# controler.net
KiCad netlist of a schematic drawn in EAGLE
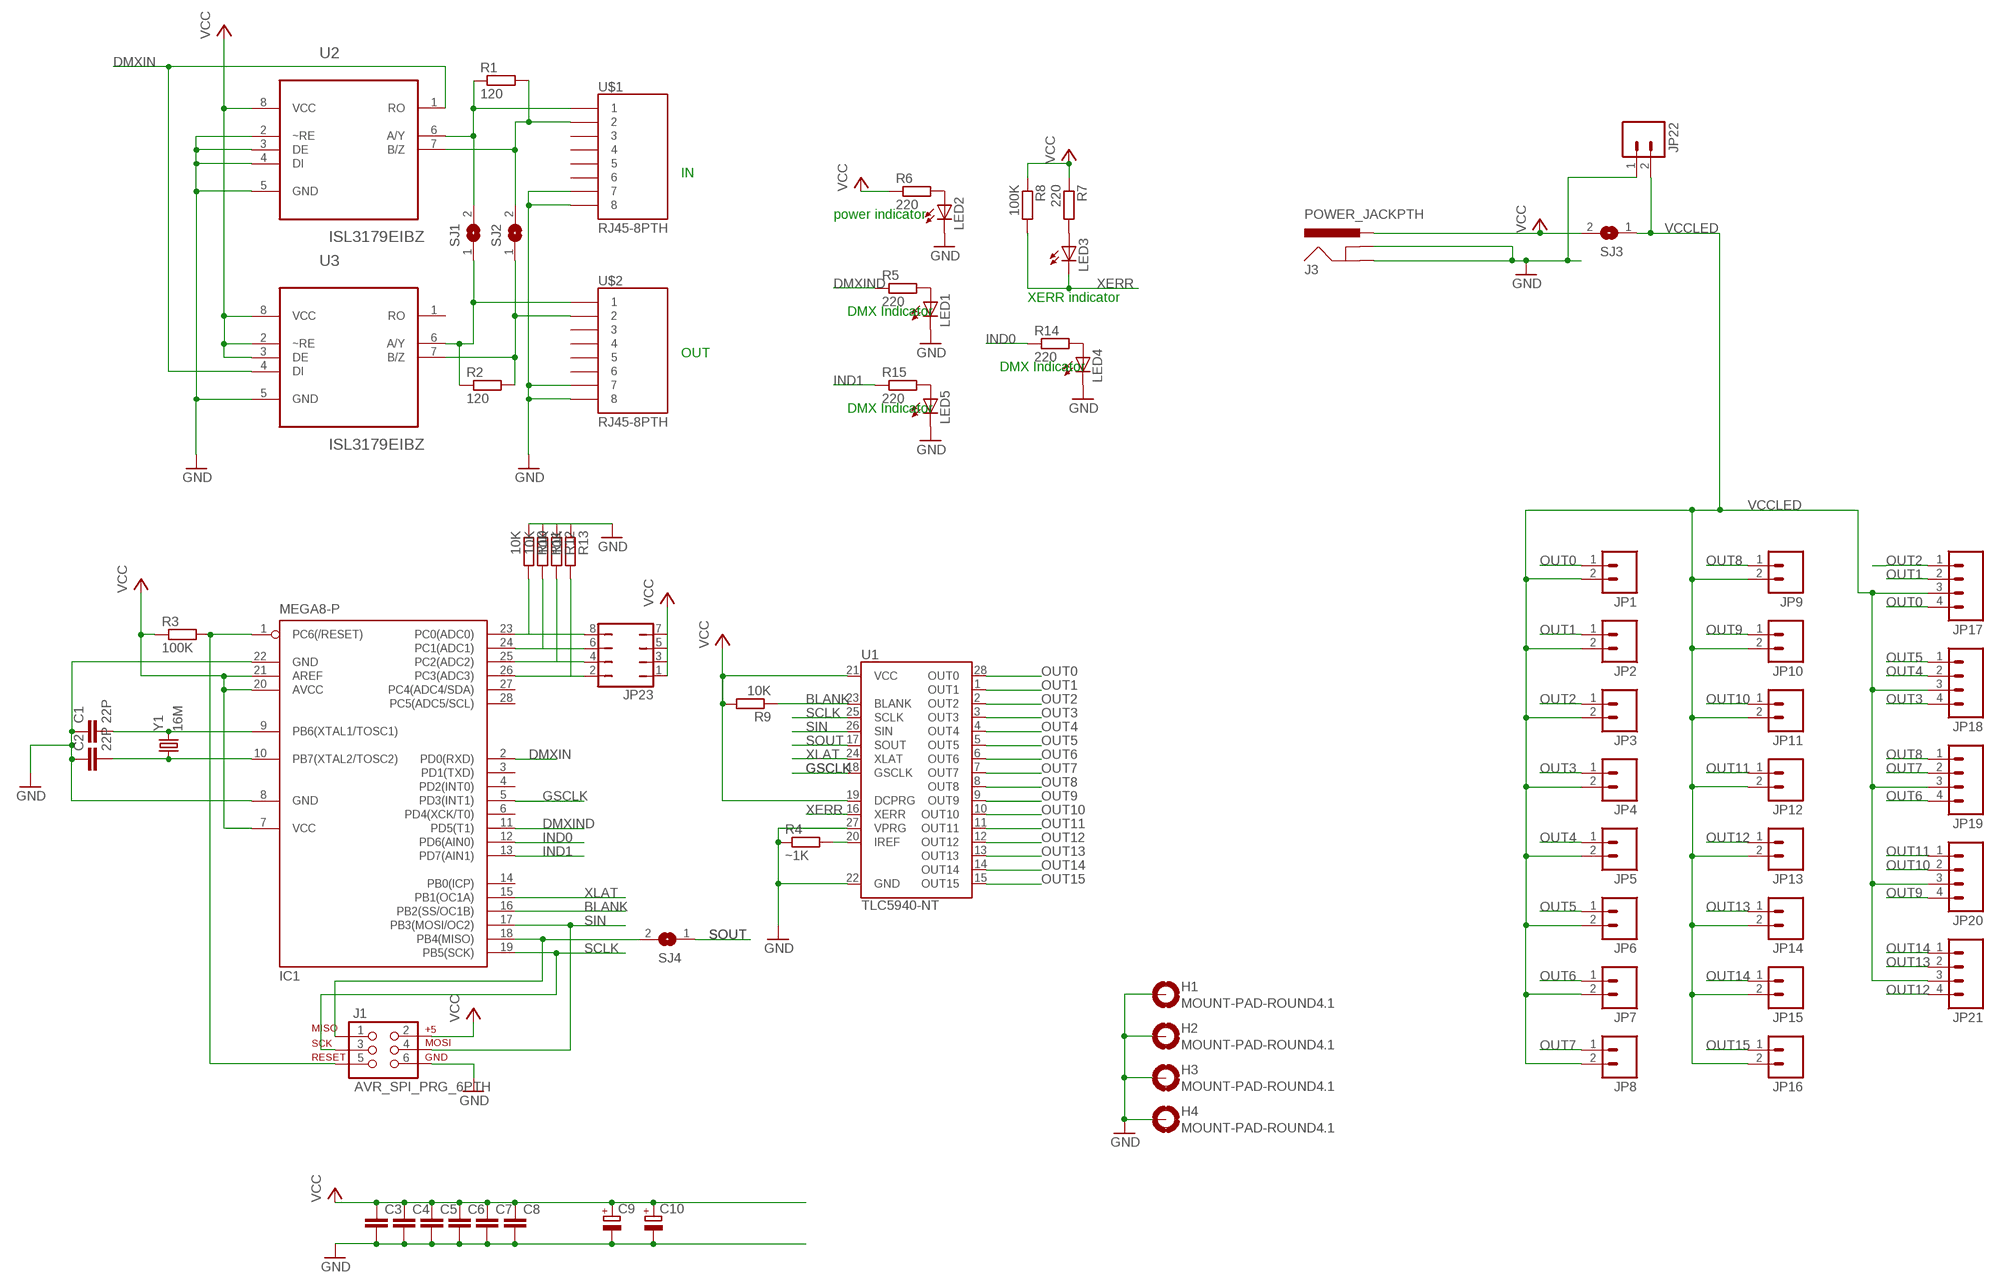
[diagram p0: schematic, sheet 1]

(export (version "E")
  (design (tool "Eeschema 10.0.6"))
  (components
    (comp (ref "C1")
      (value "22P")
      (footprint "eagle-import:C0603")
      (libsource (lib "eagle-import") (part "C-EUC0603"))
    )
    (comp (ref "C2")
      (value "22P")
      (footprint "eagle-import:C0603")
      (libsource (lib "eagle-import") (part "C-EUC0603"))
    )
    (comp (ref "C3")
      (value "C-EUC0603")
      (footprint "eagle-import:C0603")
      (libsource (lib "eagle-import") (part "resistor_C-EUC0603"))
    )
    (comp (ref "C4")
      (value "C-EUC0603")
      (footprint "eagle-import:C0603")
      (libsource (lib "eagle-import") (part "resistor_C-EUC0603"))
    )
    (comp (ref "C5")
      (value "C-EUC0603")
      (footprint "eagle-import:C0603")
      (libsource (lib "eagle-import") (part "resistor_C-EUC0603"))
    )
    (comp (ref "C6")
      (value "C-EUC0603")
      (footprint "eagle-import:C0603")
      (libsource (lib "eagle-import") (part "resistor_C-EUC0603"))
    )
    (comp (ref "C7")
      (value "C-EUC0603")
      (footprint "eagle-import:C0603")
      (libsource (lib "eagle-import") (part "resistor_C-EUC0603"))
    )
    (comp (ref "C8")
      (value "C-EUC0603")
      (footprint "eagle-import:C0603")
      (libsource (lib "eagle-import") (part "resistor_C-EUC0603"))
    )
    (comp (ref "C9")
      (value "CPOL-EUE2.5-6")
      (footprint "eagle-import:E2,5-6")
      (libsource (lib "eagle-import") (part "CPOL-EUE2.5-6"))
    )
    (comp (ref "C10")
      (value "CPOL-EUE3.5-10")
      (footprint "eagle-import:E3,5-10")
      (libsource (lib "eagle-import") (part "CPOL-EUE3.5-10"))
    )
    (comp (ref "H1")
      (value "MOUNT-PAD-ROUND4.1")
      (footprint "eagle-import:4,1-PAD")
      (libsource (lib "eagle-import") (part "MOUNT-PAD-ROUND4.1"))
    )
    (comp (ref "H2")
      (value "MOUNT-PAD-ROUND4.1")
      (footprint "eagle-import:4,1-PAD")
      (libsource (lib "eagle-import") (part "MOUNT-PAD-ROUND4.1"))
    )
    (comp (ref "H3")
      (value "MOUNT-PAD-ROUND4.1")
      (footprint "eagle-import:4,1-PAD")
      (libsource (lib "eagle-import") (part "MOUNT-PAD-ROUND4.1"))
    )
    (comp (ref "H4")
      (value "MOUNT-PAD-ROUND4.1")
      (footprint "eagle-import:4,1-PAD")
      (libsource (lib "eagle-import") (part "MOUNT-PAD-ROUND4.1"))
    )
    (comp (ref "IC1")
      (value "MEGA8-P")
      (footprint "eagle-import:DIL28-3")
      (libsource (lib "eagle-import") (part "MEGA8-P"))
    )
    (comp (ref "J1")
      (value "AVR_SPI_PRG_6PTH")
      (footprint "eagle-import:2X3")
      (libsource (lib "eagle-import") (part "AVR_SPI_PRG_6PTH"))
    )
    (comp (ref "J3")
      (value "POWER_JACKPTH")
      (footprint "eagle-import:POWER_JACK_PTH")
      (libsource (lib "eagle-import") (part "POWER_JACKPTH"))
    )
    (comp (ref "JP1")
      (value "M02POLAR")
      (footprint "eagle-import:MOLEX-1X2")
      (libsource (lib "eagle-import") (part "M02POLAR"))
    )
    (comp (ref "JP2")
      (value "M02POLAR")
      (footprint "eagle-import:MOLEX-1X2")
      (libsource (lib "eagle-import") (part "M02POLAR"))
    )
    (comp (ref "JP3")
      (value "M02POLAR")
      (footprint "eagle-import:MOLEX-1X2")
      (libsource (lib "eagle-import") (part "M02POLAR"))
    )
    (comp (ref "JP4")
      (value "M02POLAR")
      (footprint "eagle-import:MOLEX-1X2")
      (libsource (lib "eagle-import") (part "M02POLAR"))
    )
    (comp (ref "JP5")
      (value "M02POLAR")
      (footprint "eagle-import:MOLEX-1X2")
      (libsource (lib "eagle-import") (part "M02POLAR"))
    )
    (comp (ref "JP6")
      (value "M02POLAR")
      (footprint "eagle-import:MOLEX-1X2")
      (libsource (lib "eagle-import") (part "M02POLAR"))
    )
    (comp (ref "JP7")
      (value "M02POLAR")
      (footprint "eagle-import:MOLEX-1X2")
      (libsource (lib "eagle-import") (part "M02POLAR"))
    )
    (comp (ref "JP8")
      (value "M02POLAR")
      (footprint "eagle-import:MOLEX-1X2")
      (libsource (lib "eagle-import") (part "M02POLAR"))
    )
    (comp (ref "JP9")
      (value "M02POLAR")
      (footprint "eagle-import:MOLEX-1X2")
      (libsource (lib "eagle-import") (part "M02POLAR"))
    )
    (comp (ref "JP10")
      (value "M02POLAR")
      (footprint "eagle-import:MOLEX-1X2")
      (libsource (lib "eagle-import") (part "M02POLAR"))
    )
    (comp (ref "JP11")
      (value "M02POLAR")
      (footprint "eagle-import:MOLEX-1X2")
      (libsource (lib "eagle-import") (part "M02POLAR"))
    )
    (comp (ref "JP12")
      (value "M02POLAR")
      (footprint "eagle-import:MOLEX-1X2")
      (libsource (lib "eagle-import") (part "M02POLAR"))
    )
    (comp (ref "JP13")
      (value "M02POLAR")
      (footprint "eagle-import:MOLEX-1X2")
      (libsource (lib "eagle-import") (part "M02POLAR"))
    )
    (comp (ref "JP14")
      (value "M02POLAR")
      (footprint "eagle-import:MOLEX-1X2")
      (libsource (lib "eagle-import") (part "M02POLAR"))
    )
    (comp (ref "JP15")
      (value "M02POLAR")
      (footprint "eagle-import:MOLEX-1X2")
      (libsource (lib "eagle-import") (part "M02POLAR"))
    )
    (comp (ref "JP16")
      (value "M02POLAR")
      (footprint "eagle-import:MOLEX-1X2")
      (libsource (lib "eagle-import") (part "M02POLAR"))
    )
    (comp (ref "JP17")
      (value "M04POLAR")
      (footprint "eagle-import:MOLEX-1X4")
      (libsource (lib "eagle-import") (part "M04POLAR"))
    )
    (comp (ref "JP18")
      (value "M04POLAR")
      (footprint "eagle-import:MOLEX-1X4")
      (libsource (lib "eagle-import") (part "M04POLAR"))
    )
    (comp (ref "JP19")
      (value "M04POLAR")
      (footprint "eagle-import:MOLEX-1X4")
      (libsource (lib "eagle-import") (part "M04POLAR"))
    )
    (comp (ref "JP20")
      (value "M04POLAR")
      (footprint "eagle-import:MOLEX-1X4")
      (libsource (lib "eagle-import") (part "M04POLAR"))
    )
    (comp (ref "JP21")
      (value "M04POLAR")
      (footprint "eagle-import:MOLEX-1X4")
      (libsource (lib "eagle-import") (part "M04POLAR"))
    )
    (comp (ref "JP22")
      (value "M023.5MM")
      (footprint "eagle-import:SCREWTERMINAL-3.5MM-2")
      (libsource (lib "eagle-import") (part "M023.5MM"))
    )
    (comp (ref "JP23")
      (value "JP4Q")
      (footprint "eagle-import:JP4Q")
      (libsource (lib "eagle-import") (part "JP4Q"))
    )
    (comp (ref "LED1")
      (value "LEDCHIPLED_0603")
      (footprint "eagle-import:CHIPLED_0603")
      (libsource (lib "eagle-import") (part "LEDCHIPLED_0603"))
    )
    (comp (ref "LED2")
      (value "LEDCHIPLED_0603")
      (footprint "eagle-import:CHIPLED_0603")
      (libsource (lib "eagle-import") (part "LEDCHIPLED_0603"))
    )
    (comp (ref "LED3")
      (value "LEDCHIPLED_0603")
      (footprint "eagle-import:CHIPLED_0603")
      (libsource (lib "eagle-import") (part "LEDCHIPLED_0603"))
    )
    (comp (ref "LED4")
      (value "LEDCHIPLED_0603")
      (footprint "eagle-import:CHIPLED_0603")
      (libsource (lib "eagle-import") (part "LEDCHIPLED_0603"))
    )
    (comp (ref "LED5")
      (value "LEDCHIPLED_0603")
      (footprint "eagle-import:CHIPLED_0603")
      (libsource (lib "eagle-import") (part "LEDCHIPLED_0603"))
    )
    (comp (ref "R1")
      (value "120")
      (footprint "eagle-import:R0603")
      (libsource (lib "eagle-import") (part "R-EU_R0603"))
    )
    (comp (ref "R2")
      (value "120")
      (footprint "eagle-import:R0603")
      (libsource (lib "eagle-import") (part "R-EU_R0603"))
    )
    (comp (ref "R3")
      (value "100K")
      (footprint "eagle-import:R0603")
      (libsource (lib "eagle-import") (part "resistor_R-EU_R0603"))
    )
    (comp (ref "R4")
      (value "~1K")
      (footprint "eagle-import:R0603")
      (libsource (lib "eagle-import") (part "resistor_R-EU_R0603"))
    )
    (comp (ref "R5")
      (value "220")
      (footprint "eagle-import:R0603")
      (libsource (lib "eagle-import") (part "resistor_R-EU_R0603"))
    )
    (comp (ref "R6")
      (value "220")
      (footprint "eagle-import:R0603")
      (libsource (lib "eagle-import") (part "resistor_R-EU_R0603"))
    )
    (comp (ref "R7")
      (value "220")
      (footprint "eagle-import:R0603")
      (libsource (lib "eagle-import") (part "resistor_R-EU_R0603"))
    )
    (comp (ref "R8")
      (value "100K")
      (footprint "eagle-import:R0603")
      (libsource (lib "eagle-import") (part "resistor_R-EU_R0603"))
    )
    (comp (ref "R9")
      (value "10K")
      (footprint "eagle-import:R0603")
      (libsource (lib "eagle-import") (part "resistor_R-EU_R0603"))
    )
    (comp (ref "R10")
      (value "10K")
      (footprint "eagle-import:R0603")
      (libsource (lib "eagle-import") (part "resistor_R-EU_R0603"))
    )
    (comp (ref "R11")
      (value "10K")
      (footprint "eagle-import:R0603")
      (libsource (lib "eagle-import") (part "resistor_R-EU_R0603"))
    )
    (comp (ref "R12")
      (value "10K")
      (footprint "eagle-import:R0603")
      (libsource (lib "eagle-import") (part "resistor_R-EU_R0603"))
    )
    (comp (ref "R13")
      (value "10K")
      (footprint "eagle-import:R0603")
      (libsource (lib "eagle-import") (part "resistor_R-EU_R0603"))
    )
    (comp (ref "R14")
      (value "220")
      (footprint "eagle-import:R0603")
      (libsource (lib "eagle-import") (part "resistor_R-EU_R0603"))
    )
    (comp (ref "R15")
      (value "220")
      (footprint "eagle-import:R0603")
      (libsource (lib "eagle-import") (part "resistor_R-EU_R0603"))
    )
    (comp (ref "SJ1") (value "SJ") (footprint "eagle-import:SJ") (libsource (lib "eagle-import") (part "SJ")))
    (comp (ref "SJ2") (value "SJ") (footprint "eagle-import:SJ") (libsource (lib "eagle-import") (part "SJ")))
    (comp (ref "SJ3")
      (value "SJW")
      (footprint "eagle-import:SJW")
      (libsource (lib "eagle-import") (part "SJW"))
    )
    (comp (ref "SJ4") (value "SJ") (footprint "eagle-import:SJ") (libsource (lib "eagle-import") (part "SJ")))
    (comp (ref "U$1")
      (value "RJ45-8PTH")
      (footprint "eagle-import:RJ45-8")
      (libsource (lib "eagle-import") (part "RJ45-8PTH"))
    )
    (comp (ref "U$2")
      (value "RJ45-8PTH")
      (footprint "eagle-import:RJ45-8")
      (libsource (lib "eagle-import") (part "RJ45-8PTH"))
    )
    (comp (ref "U1")
      (value "TLC5940-NT")
      (footprint "eagle-import:DIL28-3")
      (libsource (lib "eagle-import") (part "TLC5940-NT"))
    )
    (comp (ref "U2")
      (value "ISL3179EIBZ")
      (footprint "eagle-import:SOIC127P600X175-8N")
      (libsource (lib "eagle-import") (part "ISL3179EIBZ"))
    )
    (comp (ref "U3")
      (value "ISL3179EIBZ")
      (footprint "eagle-import:SOIC127P600X175-8N")
      (libsource (lib "eagle-import") (part "ISL3179EIBZ"))
    )
    (comp (ref "Y1")
      (value "16M")
      (footprint "eagle-import:HC49US")
      (libsource (lib "eagle-import") (part "CRYSTALHC49US"))
    )
  )
  (nets
    (net (code "1") (name "/BLANK") (class "Default")
      (node (ref "IC1") (pin "16") (pinfunction "PB2(SS/OC1B)_16") (pintype "bidirectional"))
      (node (ref "R9") (pin "1") (pinfunction "1_1") (pintype "passive"))
      (node (ref "U1") (pin "23") (pinfunction "BLANK_23") (pintype "bidirectional"))
    )
    (net (code "2") (name "/DMXIN") (class "Default")
      (node (ref "IC1") (pin "2") (pinfunction "PD0(RXD)_2") (pintype "bidirectional"))
      (node (ref "U2") (pin "1") (pinfunction "RO_1") (pintype "output"))
      (node (ref "U3") (pin "4") (pinfunction "DI_4") (pintype "input"))
    )
    (net (code "3") (name "/DMXIND") (class "Default")
      (node (ref "IC1") (pin "11") (pinfunction "PD5(T1)_11") (pintype "bidirectional"))
      (node (ref "R5") (pin "1") (pinfunction "1_1") (pintype "passive"))
    )
    (net (code "4") (name "/GSCLK") (class "Default")
      (node (ref "IC1") (pin "5") (pinfunction "PD3(INT1)_5") (pintype "bidirectional"))
      (node (ref "U1") (pin "18") (pinfunction "GSCLK_18") (pintype "bidirectional"))
    )
    (net (code "5") (name "/IND0") (class "Default")
      (node (ref "IC1") (pin "12") (pinfunction "PD6(AIN0)_12") (pintype "bidirectional"))
      (node (ref "R14") (pin "1") (pinfunction "1_1") (pintype "passive"))
    )
    (net (code "6") (name "/IND1") (class "Default")
      (node (ref "IC1") (pin "13") (pinfunction "PD7(AIN1)_13") (pintype "bidirectional"))
      (node (ref "R15") (pin "1") (pinfunction "1_1") (pintype "passive"))
    )
    (net (code "7") (name "/OUT0") (class "Default")
      (node (ref "JP1") (pin "1") (pinfunction "1_1") (pintype "passive"))
      (node (ref "JP17") (pin "4") (pinfunction "4_4") (pintype "passive"))
      (node (ref "U1") (pin "28") (pinfunction "OUT0_28") (pintype "bidirectional"))
    )
    (net (code "8") (name "/OUT1") (class "Default")
      (node (ref "JP17") (pin "2") (pinfunction "2_2") (pintype "passive"))
      (node (ref "JP2") (pin "1") (pinfunction "1_1") (pintype "passive"))
      (node (ref "U1") (pin "1") (pinfunction "OUT1_1") (pintype "bidirectional"))
    )
    (net (code "9") (name "/OUT2") (class "Default")
      (node (ref "JP17") (pin "1") (pinfunction "1_1") (pintype "passive"))
      (node (ref "JP3") (pin "1") (pinfunction "1_1") (pintype "passive"))
      (node (ref "U1") (pin "2") (pinfunction "OUT2_2") (pintype "bidirectional"))
    )
    (net (code "10") (name "/OUT3") (class "Default")
      (node (ref "JP18") (pin "4") (pinfunction "4_4") (pintype "passive"))
      (node (ref "JP4") (pin "1") (pinfunction "1_1") (pintype "passive"))
      (node (ref "U1") (pin "3") (pinfunction "OUT3_3") (pintype "bidirectional"))
    )
    (net (code "11") (name "/OUT4") (class "Default")
      (node (ref "JP18") (pin "2") (pinfunction "2_2") (pintype "passive"))
      (node (ref "JP5") (pin "1") (pinfunction "1_1") (pintype "passive"))
      (node (ref "U1") (pin "4") (pinfunction "OUT4_4") (pintype "bidirectional"))
    )
    (net (code "12") (name "/OUT5") (class "Default")
      (node (ref "JP18") (pin "1") (pinfunction "1_1") (pintype "passive"))
      (node (ref "JP6") (pin "1") (pinfunction "1_1") (pintype "passive"))
      (node (ref "U1") (pin "5") (pinfunction "OUT5_5") (pintype "bidirectional"))
    )
    (net (code "13") (name "/OUT6") (class "Default")
      (node (ref "JP19") (pin "4") (pinfunction "4_4") (pintype "passive"))
      (node (ref "JP7") (pin "1") (pinfunction "1_1") (pintype "passive"))
      (node (ref "U1") (pin "6") (pinfunction "OUT6_6") (pintype "bidirectional"))
    )
    (net (code "14") (name "/OUT7") (class "Default")
      (node (ref "JP19") (pin "2") (pinfunction "2_2") (pintype "passive"))
      (node (ref "JP8") (pin "1") (pinfunction "1_1") (pintype "passive"))
      (node (ref "U1") (pin "7") (pinfunction "OUT7_7") (pintype "bidirectional"))
    )
    (net (code "15") (name "/OUT8") (class "Default")
      (node (ref "JP19") (pin "1") (pinfunction "1_1") (pintype "passive"))
      (node (ref "JP9") (pin "1") (pinfunction "1_1") (pintype "passive"))
      (node (ref "U1") (pin "8") (pinfunction "OUT8_8") (pintype "bidirectional"))
    )
    (net (code "16") (name "/OUT9") (class "Default")
      (node (ref "JP10") (pin "1") (pinfunction "1_1") (pintype "passive"))
      (node (ref "JP20") (pin "4") (pinfunction "4_4") (pintype "passive"))
      (node (ref "U1") (pin "9") (pinfunction "OUT9_9") (pintype "bidirectional"))
    )
    (net (code "17") (name "/OUT10") (class "Default")
      (node (ref "JP11") (pin "1") (pinfunction "1_1") (pintype "passive"))
      (node (ref "JP20") (pin "2") (pinfunction "2_2") (pintype "passive"))
      (node (ref "U1") (pin "10") (pinfunction "OUT10_10") (pintype "bidirectional"))
    )
    (net (code "18") (name "/OUT11") (class "Default")
      (node (ref "JP12") (pin "1") (pinfunction "1_1") (pintype "passive"))
      (node (ref "JP20") (pin "1") (pinfunction "1_1") (pintype "passive"))
      (node (ref "U1") (pin "11") (pinfunction "OUT11_11") (pintype "bidirectional"))
    )
    (net (code "19") (name "/OUT12") (class "Default")
      (node (ref "JP13") (pin "1") (pinfunction "1_1") (pintype "passive"))
      (node (ref "JP21") (pin "4") (pinfunction "4_4") (pintype "passive"))
      (node (ref "U1") (pin "12") (pinfunction "OUT12_12") (pintype "bidirectional"))
    )
    (net (code "20") (name "/OUT13") (class "Default")
      (node (ref "JP14") (pin "1") (pinfunction "1_1") (pintype "passive"))
      (node (ref "JP21") (pin "2") (pinfunction "2_2") (pintype "passive"))
      (node (ref "U1") (pin "13") (pinfunction "OUT13_13") (pintype "bidirectional"))
    )
    (net (code "21") (name "/OUT14") (class "Default")
      (node (ref "JP15") (pin "1") (pinfunction "1_1") (pintype "passive"))
      (node (ref "JP21") (pin "1") (pinfunction "1_1") (pintype "passive"))
      (node (ref "U1") (pin "14") (pinfunction "OUT14_14") (pintype "bidirectional"))
    )
    (net (code "22") (name "/OUT15") (class "Default")
      (node (ref "JP16") (pin "1") (pinfunction "1_1") (pintype "passive"))
      (node (ref "U1") (pin "15") (pinfunction "OUT15_15") (pintype "bidirectional"))
    )
    (net (code "23") (name "/SCLK") (class "Default")
      (node (ref "IC1") (pin "19") (pinfunction "PB5(SCK)_19") (pintype "bidirectional"))
      (node (ref "J1") (pin "3") (pinfunction "3_3") (pintype "passive"))
      (node (ref "U1") (pin "25") (pinfunction "SCLK_25") (pintype "bidirectional"))
    )
    (net (code "24") (name "/SIN") (class "Default")
      (node (ref "IC1") (pin "17") (pinfunction "PB3(MOSI/OC2)_17") (pintype "bidirectional"))
      (node (ref "J1") (pin "4") (pinfunction "4_4") (pintype "passive"))
      (node (ref "U1") (pin "26") (pinfunction "SIN_26") (pintype "bidirectional"))
    )
    (net (code "25") (name "/SOUT") (class "Default")
      (node (ref "SJ4") (pin "1") (pinfunction "1_1") (pintype "passive"))
      (node (ref "U1") (pin "17") (pinfunction "SOUT_17") (pintype "bidirectional"))
    )
    (net (code "26") (name "/VCCLED") (class "Default")
      (node (ref "JP1") (pin "2") (pinfunction "2_2") (pintype "passive"))
      (node (ref "JP10") (pin "2") (pinfunction "2_2") (pintype "passive"))
      (node (ref "JP11") (pin "2") (pinfunction "2_2") (pintype "passive"))
      (node (ref "JP12") (pin "2") (pinfunction "2_2") (pintype "passive"))
      (node (ref "JP13") (pin "2") (pinfunction "2_2") (pintype "passive"))
      (node (ref "JP14") (pin "2") (pinfunction "2_2") (pintype "passive"))
      (node (ref "JP15") (pin "2") (pinfunction "2_2") (pintype "passive"))
      (node (ref "JP16") (pin "2") (pinfunction "2_2") (pintype "passive"))
      (node (ref "JP17") (pin "3") (pinfunction "3_3") (pintype "passive"))
      (node (ref "JP18") (pin "3") (pinfunction "3_3") (pintype "passive"))
      (node (ref "JP19") (pin "3") (pinfunction "3_3") (pintype "passive"))
      (node (ref "JP2") (pin "2") (pinfunction "2_2") (pintype "passive"))
      (node (ref "JP20") (pin "3") (pinfunction "3_3") (pintype "passive"))
      (node (ref "JP21") (pin "3") (pinfunction "3_3") (pintype "passive"))
      (node (ref "JP22") (pin "2") (pinfunction "2_2") (pintype "passive"))
      (node (ref "JP3") (pin "2") (pinfunction "2_2") (pintype "passive"))
      (node (ref "JP4") (pin "2") (pinfunction "2_2") (pintype "passive"))
      (node (ref "JP5") (pin "2") (pinfunction "2_2") (pintype "passive"))
      (node (ref "JP6") (pin "2") (pinfunction "2_2") (pintype "passive"))
      (node (ref "JP7") (pin "2") (pinfunction "2_2") (pintype "passive"))
      (node (ref "JP8") (pin "2") (pinfunction "2_2") (pintype "passive"))
      (node (ref "JP9") (pin "2") (pinfunction "2_2") (pintype "passive"))
      (node (ref "SJ3") (pin "1") (pinfunction "1_1") (pintype "passive"))
    )
    (net (code "27") (name "/XERR") (class "Default")
      (node (ref "LED3") (pin "C") (pinfunction "C_C") (pintype "passive"))
      (node (ref "R8") (pin "2") (pinfunction "2_2") (pintype "passive"))
      (node (ref "U1") (pin "16") (pinfunction "XERR_16") (pintype "bidirectional"))
    )
    (net (code "28") (name "/XLAT") (class "Default")
      (node (ref "IC1") (pin "15") (pinfunction "PB1(OC1A)_15") (pintype "bidirectional"))
      (node (ref "U1") (pin "24") (pinfunction "XLAT_24") (pintype "bidirectional"))
    )
    (net (code "29") (name "GND") (class "Default")
      (node (ref "C1") (pin "1") (pinfunction "1_1") (pintype "passive"))
      (node (ref "C10") (pin "-") (pinfunction "-_-") (pintype "passive"))
      (node (ref "C2") (pin "1") (pinfunction "1_1") (pintype "passive"))
      (node (ref "C3") (pin "2") (pinfunction "2_2") (pintype "passive"))
      (node (ref "C4") (pin "2") (pinfunction "2_2") (pintype "passive"))
      (node (ref "C5") (pin "2") (pinfunction "2_2") (pintype "passive"))
      (node (ref "C6") (pin "2") (pinfunction "2_2") (pintype "passive"))
      (node (ref "C7") (pin "2") (pinfunction "2_2") (pintype "passive"))
      (node (ref "C8") (pin "2") (pinfunction "2_2") (pintype "passive"))
      (node (ref "C9") (pin "-") (pinfunction "-_-") (pintype "passive"))
      (node (ref "H1") (pin "B4,1") (pinfunction "MOUNT_B4,1") (pintype "passive"))
      (node (ref "H2") (pin "B4,1") (pinfunction "MOUNT_B4,1") (pintype "passive"))
      (node (ref "H3") (pin "B4,1") (pinfunction "MOUNT_B4,1") (pintype "passive"))
      (node (ref "H4") (pin "B4,1") (pinfunction "MOUNT_B4,1") (pintype "passive"))
      (node (ref "IC1") (pin "22") (pinfunction "GND_22") (pintype "power_in"))
      (node (ref "IC1") (pin "8") (pinfunction "GND_8") (pintype "power_in"))
      (node (ref "J1") (pin "6") (pinfunction "6_6") (pintype "passive"))
      (node (ref "J3") (pin "GND") (pinfunction "GND_GND") (pintype "bidirectional"))
      (node (ref "J3") (pin "GNDBREAK") (pinfunction "GNDBREAK_GNDBREAK") (pintype "bidirectional"))
      (node (ref "JP22") (pin "1") (pinfunction "1_1") (pintype "passive"))
      (node (ref "LED1") (pin "C") (pinfunction "C_C") (pintype "passive"))
      (node (ref "LED2") (pin "C") (pinfunction "C_C") (pintype "passive"))
      (node (ref "LED4") (pin "C") (pinfunction "C_C") (pintype "passive"))
      (node (ref "LED5") (pin "C") (pinfunction "C_C") (pintype "passive"))
      (node (ref "R10") (pin "1") (pinfunction "1_1") (pintype "passive"))
      (node (ref "R11") (pin "1") (pinfunction "1_1") (pintype "passive"))
      (node (ref "R12") (pin "1") (pinfunction "1_1") (pintype "passive"))
      (node (ref "R13") (pin "1") (pinfunction "1_1") (pintype "passive"))
      (node (ref "R4") (pin "1") (pinfunction "1_1") (pintype "passive"))
      (node (ref "U$1") (pin "7") (pinfunction "7_7") (pintype "bidirectional"))
      (node (ref "U$1") (pin "8") (pinfunction "8_8") (pintype "bidirectional"))
      (node (ref "U$2") (pin "7") (pinfunction "7_7") (pintype "bidirectional"))
      (node (ref "U$2") (pin "8") (pinfunction "8_8") (pintype "bidirectional"))
      (node (ref "U1") (pin "22") (pinfunction "GND_22") (pintype "bidirectional"))
      (node (ref "U1") (pin "27") (pinfunction "VPRG_27") (pintype "bidirectional"))
      (node (ref "U2") (pin "2") (pinfunction "~{RE}_2") (pintype "input"))
      (node (ref "U2") (pin "3") (pinfunction "DE_3") (pintype "input"))
      (node (ref "U2") (pin "4") (pinfunction "DI_4") (pintype "input"))
      (node (ref "U2") (pin "5") (pinfunction "GND_5") (pintype "passive"))
      (node (ref "U3") (pin "5") (pinfunction "GND_5") (pintype "passive"))
    )
    (net (code "30") (name "Net-(IC1-PB4(MISO))") (class "Default")
      (node (ref "IC1") (pin "18") (pinfunction "PB4(MISO)_18") (pintype "bidirectional"))
      (node (ref "J1") (pin "1") (pinfunction "1_1") (pintype "passive"))
      (node (ref "SJ4") (pin "2") (pinfunction "2_2") (pintype "passive"))
    )
    (net (code "31") (name "Net-(IC1-PB6(XTAL1{slash}TOSC1))") (class "Default")
      (node (ref "C1") (pin "2") (pinfunction "2_2") (pintype "passive"))
      (node (ref "IC1") (pin "9") (pinfunction "PB6(XTAL1/TOSC1)_9") (pintype "bidirectional"))
      (node (ref "Y1") (pin "2") (pinfunction "2_2") (pintype "passive"))
    )
    (net (code "32") (name "Net-(IC1-PB7(XTAL2{slash}TOSC2))") (class "Default")
      (node (ref "C2") (pin "2") (pinfunction "2_2") (pintype "passive"))
      (node (ref "IC1") (pin "10") (pinfunction "PB7(XTAL2/TOSC2)_10") (pintype "bidirectional"))
      (node (ref "Y1") (pin "1") (pinfunction "1_1") (pintype "passive"))
    )
    (net (code "33") (name "Net-(IC1-PC0(ADC0))") (class "Default")
      (node (ref "IC1") (pin "23") (pinfunction "PC0(ADC0)_23") (pintype "bidirectional"))
      (node (ref "JP23") (pin "8") (pinfunction "8_8") (pintype "passive"))
      (node (ref "R10") (pin "2") (pinfunction "2_2") (pintype "passive"))
    )
    (net (code "34") (name "Net-(IC1-PC1(ADC1))") (class "Default")
      (node (ref "IC1") (pin "24") (pinfunction "PC1(ADC1)_24") (pintype "bidirectional"))
      (node (ref "JP23") (pin "6") (pinfunction "6_6") (pintype "passive"))
      (node (ref "R11") (pin "2") (pinfunction "2_2") (pintype "passive"))
    )
    (net (code "35") (name "Net-(IC1-PC2(ADC2))") (class "Default")
      (node (ref "IC1") (pin "25") (pinfunction "PC2(ADC2)_25") (pintype "bidirectional"))
      (node (ref "JP23") (pin "4") (pinfunction "4_4") (pintype "passive"))
      (node (ref "R12") (pin "2") (pinfunction "2_2") (pintype "passive"))
    )
    (net (code "36") (name "Net-(IC1-PC3(ADC3))") (class "Default")
      (node (ref "IC1") (pin "26") (pinfunction "PC3(ADC3)_26") (pintype "bidirectional"))
      (node (ref "JP23") (pin "2") (pinfunction "2_2") (pintype "passive"))
      (node (ref "R13") (pin "2") (pinfunction "2_2") (pintype "passive"))
    )
    (net (code "37") (name "Net-(IC1-PC6({slash}RESET))") (class "Default")
      (node (ref "IC1") (pin "1") (pinfunction "PC6(/RESET)_1") (pintype "bidirectional"))
      (node (ref "J1") (pin "5") (pinfunction "5_5") (pintype "passive"))
      (node (ref "R3") (pin "2") (pinfunction "2_2") (pintype "passive"))
    )
    (net (code "38") (name "Net-(LED1-PadA)") (class "Default")
      (node (ref "LED1") (pin "A") (pinfunction "A_A") (pintype "passive"))
      (node (ref "R5") (pin "2") (pinfunction "2_2") (pintype "passive"))
    )
    (net (code "39") (name "Net-(LED2-PadA)") (class "Default")
      (node (ref "LED2") (pin "A") (pinfunction "A_A") (pintype "passive"))
      (node (ref "R6") (pin "2") (pinfunction "2_2") (pintype "passive"))
    )
    (net (code "40") (name "Net-(LED3-PadA)") (class "Default")
      (node (ref "LED3") (pin "A") (pinfunction "A_A") (pintype "passive"))
      (node (ref "R7") (pin "2") (pinfunction "2_2") (pintype "passive"))
    )
    (net (code "41") (name "Net-(LED4-PadA)") (class "Default")
      (node (ref "LED4") (pin "A") (pinfunction "A_A") (pintype "passive"))
      (node (ref "R14") (pin "2") (pinfunction "2_2") (pintype "passive"))
    )
    (net (code "42") (name "Net-(LED5-PadA)") (class "Default")
      (node (ref "LED5") (pin "A") (pinfunction "A_A") (pintype "passive"))
      (node (ref "R15") (pin "2") (pinfunction "2_2") (pintype "passive"))
    )
    (net (code "43") (name "Net-(U1-IREF)") (class "Default")
      (node (ref "R4") (pin "2") (pinfunction "2_2") (pintype "passive"))
      (node (ref "U1") (pin "20") (pinfunction "IREF_20") (pintype "bidirectional"))
    )
    (net (code "44") (name "Net-(U2-A{slash}Y)") (class "Default")
      (node (ref "R1") (pin "1") (pinfunction "1_1") (pintype "passive"))
      (node (ref "SJ1") (pin "2") (pinfunction "2_2") (pintype "passive"))
      (node (ref "U$1") (pin "1") (pinfunction "1_1") (pintype "bidirectional"))
      (node (ref "U2") (pin "6") (pinfunction "A/Y_6") (pintype "bidirectional"))
    )
    (net (code "45") (name "Net-(U2-B{slash}Z)") (class "Default")
      (node (ref "R1") (pin "2") (pinfunction "2_2") (pintype "passive"))
      (node (ref "SJ2") (pin "2") (pinfunction "2_2") (pintype "passive"))
      (node (ref "U$1") (pin "2") (pinfunction "2_2") (pintype "bidirectional"))
      (node (ref "U2") (pin "7") (pinfunction "B/Z_7") (pintype "bidirectional"))
    )
    (net (code "46") (name "Net-(U3-A{slash}Y)") (class "Default")
      (node (ref "R2") (pin "1") (pinfunction "1_1") (pintype "passive"))
      (node (ref "SJ1") (pin "1") (pinfunction "1_1") (pintype "passive"))
      (node (ref "U$2") (pin "1") (pinfunction "1_1") (pintype "bidirectional"))
      (node (ref "U3") (pin "6") (pinfunction "A/Y_6") (pintype "bidirectional"))
    )
    (net (code "47") (name "Net-(U3-B{slash}Z)") (class "Default")
      (node (ref "R2") (pin "2") (pinfunction "2_2") (pintype "passive"))
      (node (ref "SJ2") (pin "1") (pinfunction "1_1") (pintype "passive"))
      (node (ref "U$2") (pin "2") (pinfunction "2_2") (pintype "bidirectional"))
      (node (ref "U3") (pin "7") (pinfunction "B/Z_7") (pintype "bidirectional"))
    )
    (net (code "48") (name "VCC") (class "Default")
      (node (ref "C10") (pin "+") (pinfunction "+_+") (pintype "passive"))
      (node (ref "C3") (pin "1") (pinfunction "1_1") (pintype "passive"))
      (node (ref "C4") (pin "1") (pinfunction "1_1") (pintype "passive"))
      (node (ref "C5") (pin "1") (pinfunction "1_1") (pintype "passive"))
      (node (ref "C6") (pin "1") (pinfunction "1_1") (pintype "passive"))
      (node (ref "C7") (pin "1") (pinfunction "1_1") (pintype "passive"))
      (node (ref "C8") (pin "1") (pinfunction "1_1") (pintype "passive"))
      (node (ref "C9") (pin "+") (pinfunction "+_+") (pintype "passive"))
      (node (ref "IC1") (pin "20") (pinfunction "AVCC_20") (pintype "power_in"))
      (node (ref "IC1") (pin "21") (pinfunction "AREF_21") (pintype "passive"))
      (node (ref "IC1") (pin "7") (pinfunction "VCC_7") (pintype "power_in"))
      (node (ref "J1") (pin "2") (pinfunction "2_2") (pintype "passive"))
      (node (ref "J3") (pin "PWR") (pinfunction "PWR_PWR") (pintype "bidirectional"))
      (node (ref "JP23") (pin "1") (pinfunction "1_1") (pintype "passive"))
      (node (ref "JP23") (pin "3") (pinfunction "3_3") (pintype "passive"))
      (node (ref "JP23") (pin "5") (pinfunction "5_5") (pintype "passive"))
      (node (ref "JP23") (pin "7") (pinfunction "7_7") (pintype "passive"))
      (node (ref "R3") (pin "1") (pinfunction "1_1") (pintype "passive"))
      (node (ref "R6") (pin "1") (pinfunction "1_1") (pintype "passive"))
      (node (ref "R7") (pin "1") (pinfunction "1_1") (pintype "passive"))
      (node (ref "R8") (pin "1") (pinfunction "1_1") (pintype "passive"))
      (node (ref "R9") (pin "2") (pinfunction "2_2") (pintype "passive"))
      (node (ref "SJ3") (pin "2") (pinfunction "2_2") (pintype "passive"))
      (node (ref "U1") (pin "19") (pinfunction "DCPRG_19") (pintype "bidirectional"))
      (node (ref "U1") (pin "21") (pinfunction "VCC_21") (pintype "bidirectional"))
      (node (ref "U2") (pin "8") (pinfunction "VCC_8") (pintype "power_in"))
      (node (ref "U3") (pin "2") (pinfunction "~{RE}_2") (pintype "input"))
      (node (ref "U3") (pin "3") (pinfunction "DE_3") (pintype "input"))
      (node (ref "U3") (pin "8") (pinfunction "VCC_8") (pintype "power_in"))
    )
    (net (code "49") (name "unconnected-(IC1-PB0(ICP)-Pad14)") (class "Default")
      (node (ref "IC1") (pin "14") (pinfunction "PB0(ICP)_14") (pintype "bidirectional"))
    )
    (net (code "50") (name "unconnected-(IC1-PC4(ADC4{slash}SDA)-Pad27)") (class "Default")
      (node (ref "IC1") (pin "27") (pinfunction "PC4(ADC4/SDA)_27") (pintype "bidirectional"))
    )
    (net (code "51") (name "unconnected-(IC1-PC5(ADC5{slash}SCL)-Pad28)") (class "Default")
      (node (ref "IC1") (pin "28") (pinfunction "PC5(ADC5/SCL)_28") (pintype "bidirectional"))
    )
    (net (code "52") (name "unconnected-(IC1-PD1(TXD)-Pad3)") (class "Default")
      (node (ref "IC1") (pin "3") (pinfunction "PD1(TXD)_3") (pintype "bidirectional"))
    )
    (net (code "53") (name "unconnected-(IC1-PD2(INT0)-Pad4)") (class "Default")
      (node (ref "IC1") (pin "4") (pinfunction "PD2(INT0)_4") (pintype "bidirectional"))
    )
    (net (code "54") (name "unconnected-(IC1-PD4(XCK{slash}T0)-Pad6)") (class "Default")
      (node (ref "IC1") (pin "6") (pinfunction "PD4(XCK/T0)_6") (pintype "bidirectional"))
    )
    (net (code "55") (name "unconnected-(U$1-Pad3)") (class "Default")
      (node (ref "U$1") (pin "3") (pinfunction "3_3") (pintype "bidirectional"))
    )
    (net (code "56") (name "unconnected-(U$1-Pad4)") (class "Default")
      (node (ref "U$1") (pin "4") (pinfunction "4_4") (pintype "bidirectional"))
    )
    (net (code "57") (name "unconnected-(U$1-Pad5)") (class "Default")
      (node (ref "U$1") (pin "5") (pinfunction "5_5") (pintype "bidirectional"))
    )
    (net (code "58") (name "unconnected-(U$1-Pad6)") (class "Default")
      (node (ref "U$1") (pin "6") (pinfunction "6_6") (pintype "bidirectional"))
    )
    (net (code "59") (name "unconnected-(U$2-Pad3)") (class "Default")
      (node (ref "U$2") (pin "3") (pinfunction "3_3") (pintype "bidirectional"))
    )
    (net (code "60") (name "unconnected-(U$2-Pad4)") (class "Default")
      (node (ref "U$2") (pin "4") (pinfunction "4_4") (pintype "bidirectional"))
    )
    (net (code "61") (name "unconnected-(U$2-Pad5)") (class "Default")
      (node (ref "U$2") (pin "5") (pinfunction "5_5") (pintype "bidirectional"))
    )
    (net (code "62") (name "unconnected-(U$2-Pad6)") (class "Default")
      (node (ref "U$2") (pin "6") (pinfunction "6_6") (pintype "bidirectional"))
    )
    (net (code "63") (name "unconnected-(U3-RO-Pad1)") (class "Default")
      (node (ref "U3") (pin "1") (pinfunction "RO_1") (pintype "output"))
    )
  )
)
